# ivt33_kuznecov_list2_9var.net
KiCad netlist of a schematic drawn in Altium Designer
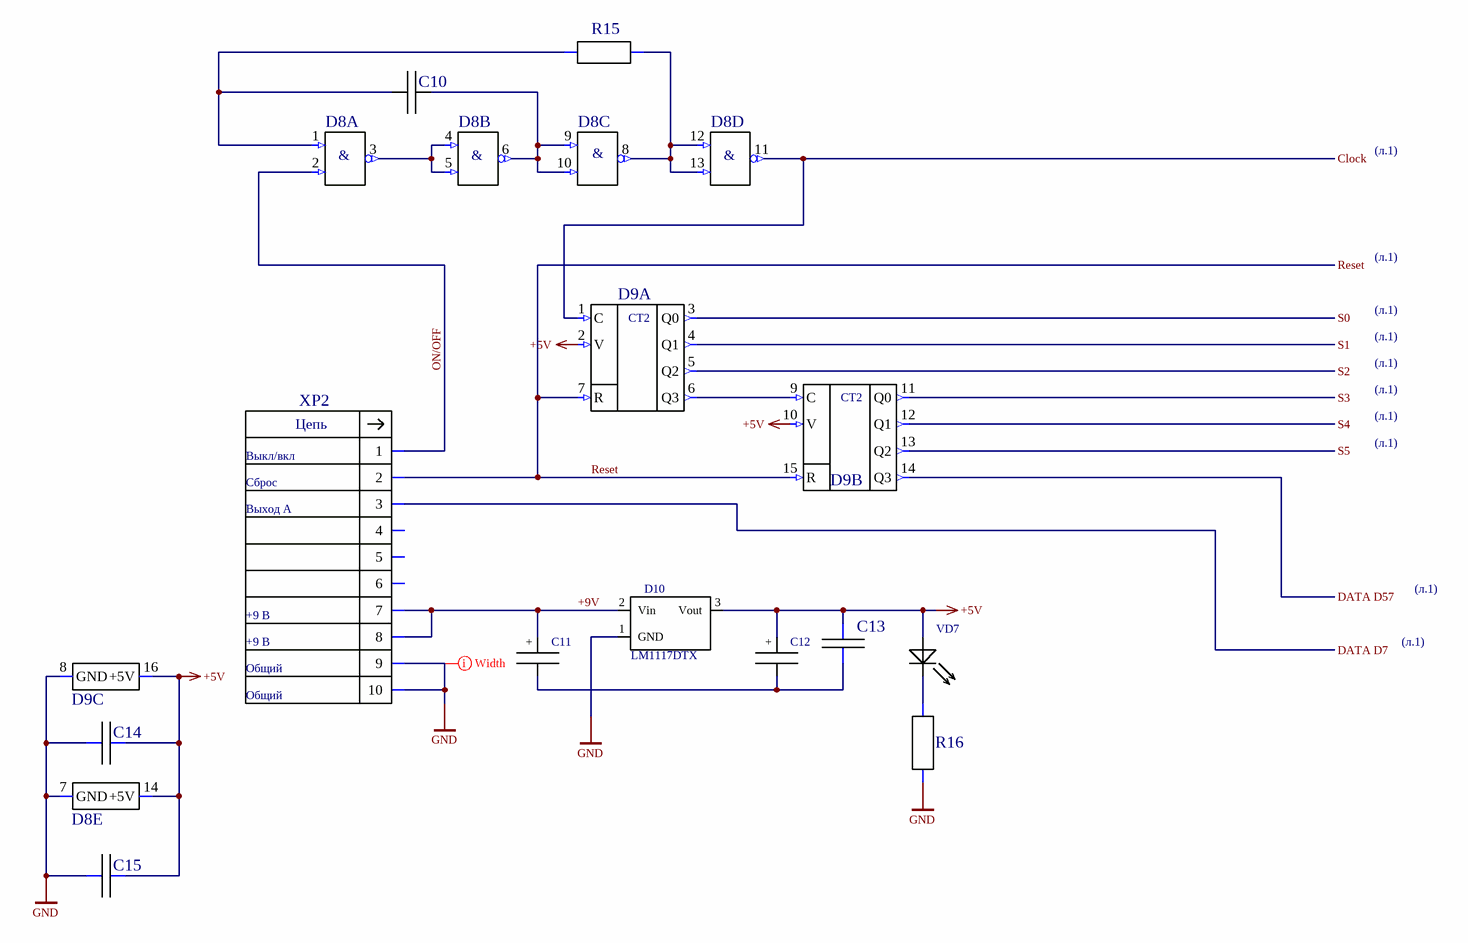
[diagram p0: ivt33_kuznecov_list2_9var.SchDoc]

(export (version "E")
  (design (tool "Eeschema 10.0.6"))
  (components
    (comp (ref "C10")
      (value "1210")
      (footprint "K10-79_3.2_2.5(1210)")
      (description "Чип конденсатор 1210 Н30 ряд Е6")
      (fields (field (name "MANUFACTURER") "ООО \"Кулон\"") (field (name "TOLERANCE") "±20%"))
      (libsource (lib "Int_Library_for_Lessons_3") (part "К10-79_1210_Н30"))
    )
    (comp (ref "C11")
      (value "*")
      (footprint "CA010M0010REB-0405")
      (description "Электролитический SND")
      (libsource (lib "*") (part "CA010M0010REB-0405"))
    )
    (comp (ref "C12")
      (value "*")
      (footprint "CA010M0010REB-0405")
      (description "Электролитический SND")
      (libsource (lib "*") (part "CA010M0010REB-0405"))
    )
    (comp (ref "C13")
      (value "~")
      (footprint "0805_N")
      (description "Чип конденсатор 0805 Н90 ряд Е6")
      (fields
        (field (name "MANUFACTURER") "ООО \"Кулон\"")
        (field (name "TOLERANCE") "+80%-20%")
        (field (name "CREATED_BY") "Желобаев")
      )
      (libsource (lib "Int_Library_for_Lessons_3") (part "К10-79_0805_Н90"))
    )
    (comp (ref "C14")
      (value "~")
      (footprint "0805_N")
      (description "Чип конденсатор 0805 Н90 ряд Е6")
      (fields
        (field (name "MANUFACTURER") "ООО \"Кулон\"")
        (field (name "TOLERANCE") "+80%-20%")
        (field (name "CREATED_BY") "Желобаев")
      )
      (libsource (lib "Int_Library_for_Lessons_3") (part "К10-79_0805_Н90"))
    )
    (comp (ref "C15")
      (value "~")
      (footprint "0805_N")
      (description "Чип конденсатор 0805 Н90 ряд Е6")
      (fields
        (field (name "MANUFACTURER") "ООО \"Кулон\"")
        (field (name "TOLERANCE") "+80%-20%")
        (field (name "CREATED_BY") "Желобаев")
      )
      (libsource (lib "Int_Library_for_Lessons_3") (part "К10-79_0805_Н90"))
    )
    (comp (ref "D8")
      (value "74AC00SC")
      (footprint "SO14-N")
      (description "4 элемента 2И-НЕ TTL SOIC-14")
      (fields (field (name "MANUFACTURER") "ON Semiconductor") (field (name "CREATED_BY") "Желобаев"))
      (libsource (lib "Int_Library_for_Lessons_3") (part "74AC00SC"))
    )
    (comp (ref "D9")
      (value "~")
      (footprint "SOIC-16W-N")
      (description "Два двоичных счетчика")
      (fields (field (name "MANUFACTURER") "Motorola") (field (name "CREATED_BY") "Желобаев"))
      (libsource (lib "Int_Library_for_Lessons_3") (part "MC14520BDWG"))
    )
    (comp (ref "D10")
      (value "LM1117DTX")
      (footprint "LM1117DTX-5.0/NOPB")
      (libsource (lib "*") (part "LT1117"))
    )
    (comp (ref "R15")
      (value "0805")
      (footprint "RES_0805_2012_N")
      (description "Резистор от 0,75 Ом до 2 МОм")
      (fields
        (field (name "MANUFACTURER") "ОАО \"НПО \"Эркон\"")
        (field (name "TOLERANCE") "5%")
        (field (name "CREATED_BY") "Желобаев")
      )
      (libsource (lib "Int_Library_for_Lessons_3") (part "Р1-12-0,125-5%"))
    )
    (comp (ref "R16")
      (value "~")
      (footprint "RES_0603_1608_N")
      (description "Резистор от 0,75 Ом до 10 МОм")
      (fields
        (field (name "MANUFACTURER") "ОАО \"НПО \"Эркон\"")
        (field (name "TOLERANCE") "5%")
        (field (name "CREATED_BY") "Желобаев")
      )
      (libsource (lib "Int_Library_for_Lessons_3") (part "Р1-12-0,1-5%"))
    )
    (comp (ref "VD7")
      (value "*")
      (footprint "LED_5mm")
      (description "Светодиод,5мм,жёлтый")
      (libsource (lib "*") (part "521-9466"))
    )
    (comp (ref "XP2")
      (value "TE_1-1634689-0")
      (footprint "BH-10R")
      (description "Вилка типа BH-10R угловая правая двухрядная 2х5х2.54")
      (fields (field (name "MANUFACTURER") "TE Connectivity") (field (name "CREATED_BY") "Желобаев"))
      (libsource (lib "Int_Library_for_Lessons_3") (part "TE_1-1634689-0"))
    )
  )
  (nets
    (net (code "1") (name "+5V") (class "Default")
      (node (ref "C12") (pin "+") (pinfunction "+_+") (pintype "passive"))
      (node (ref "C13") (pin "2") (pinfunction "2_2") (pintype "passive"))
      (node (ref "C14") (pin "2") (pinfunction "2_2") (pintype "passive"))
      (node (ref "C15") (pin "2") (pinfunction "2_2") (pintype "passive"))
      (node (ref "D10") (pin "3") (pinfunction "Vout_3") (pintype "power_in"))
      (node (ref "D8") (pin "14") (pinfunction "+5V_14") (pintype "power_in"))
      (node (ref "D9") (pin "10") (pinfunction "V_10") (pintype "input"))
      (node (ref "D9") (pin "16") (pinfunction "+5V_16") (pintype "power_in"))
      (node (ref "D9") (pin "2") (pinfunction "V_2") (pintype "input"))
      (node (ref "VD7") (pin "A") (pinfunction "A_A") (pintype "passive"))
    )
    (net (code "2") (name "/+9V") (class "Default")
      (node (ref "C11") (pin "+") (pinfunction "+_+") (pintype "passive"))
      (node (ref "D10") (pin "2") (pinfunction "Vin_2") (pintype "power_in"))
      (node (ref "XP2") (pin "7") (pinfunction "7_7") (pintype "passive"))
      (node (ref "XP2") (pin "8") (pinfunction "8_8") (pintype "passive"))
    )
    (net (code "3") (name "/Clock") (class "Default")
      (node (ref "D8") (pin "11") (pinfunction "Out_11") (pintype "output"))
      (node (ref "D9") (pin "1") (pinfunction "C_1") (pintype "input"))
    )
    (net (code "4") (name "/DATA D7") (class "Default")
      (node (ref "XP2") (pin "3") (pinfunction "3_3") (pintype "passive"))
    )
    (net (code "5") (name "/DATA D57") (class "Default")
      (node (ref "D9") (pin "14") (pinfunction "Q3_14") (pintype "output"))
    )
    (net (code "6") (name "/ON{slash}OFF") (class "Default")
      (node (ref "D8") (pin "2") (pinfunction "In2_2") (pintype "input"))
      (node (ref "XP2") (pin "1") (pinfunction "1_1") (pintype "passive"))
    )
    (net (code "7") (name "/Reset") (class "Default")
      (node (ref "D9") (pin "15") (pinfunction "R_15") (pintype "input"))
      (node (ref "D9") (pin "7") (pinfunction "R_7") (pintype "input"))
      (node (ref "XP2") (pin "2") (pinfunction "2_2") (pintype "passive"))
    )
    (net (code "8") (name "/S0") (class "Default")
      (node (ref "D9") (pin "3") (pinfunction "Q0_3") (pintype "output"))
    )
    (net (code "9") (name "/S1") (class "Default")
      (node (ref "D9") (pin "4") (pinfunction "Q1_4") (pintype "output"))
    )
    (net (code "10") (name "/S2") (class "Default")
      (node (ref "D9") (pin "5") (pinfunction "Q2_5") (pintype "output"))
    )
    (net (code "11") (name "/S3") (class "Default")
      (node (ref "D9") (pin "11") (pinfunction "Q0_11") (pintype "output"))
    )
    (net (code "12") (name "/S4") (class "Default")
      (node (ref "D9") (pin "12") (pinfunction "Q1_12") (pintype "output"))
    )
    (net (code "13") (name "/S5") (class "Default")
      (node (ref "D9") (pin "13") (pinfunction "Q2_13") (pintype "output"))
    )
    (net (code "14") (name "GND") (class "Default")
      (node (ref "C14") (pin "1") (pinfunction "1_1") (pintype "passive"))
      (node (ref "C15") (pin "1") (pinfunction "1_1") (pintype "passive"))
      (node (ref "D10") (pin "1") (pinfunction "GND_1") (pintype "power_in"))
      (node (ref "D8") (pin "7") (pinfunction "GND_7") (pintype "power_in"))
      (node (ref "D9") (pin "8") (pinfunction "GND_8") (pintype "power_in"))
      (node (ref "R16") (pin "1") (pinfunction "1_1") (pintype "passive"))
      (node (ref "XP2") (pin "10") (pinfunction "10_10") (pintype "passive"))
      (node (ref "XP2") (pin "9") (pinfunction "9_9") (pintype "passive"))
    )
    (net (code "15") (name "Net-(C11-Pad-)") (class "Default")
      (node (ref "C11") (pin "-") (pinfunction "-_-") (pintype "passive"))
      (node (ref "C12") (pin "-") (pinfunction "-_-") (pintype "passive"))
      (node (ref "C13") (pin "1") (pinfunction "1_1") (pintype "passive"))
    )
    (net (code "16") (name "Net-(D8A-In1)") (class "Default")
      (node (ref "C10") (pin "1") (pinfunction "1_1") (pintype "passive"))
      (node (ref "D8") (pin "1") (pinfunction "In1_1") (pintype "input"))
      (node (ref "R15") (pin "1") (pinfunction "1_1") (pintype "passive"))
    )
    (net (code "17") (name "Net-(D8A-Out)") (class "Default")
      (node (ref "D8") (pin "3") (pinfunction "Out_3") (pintype "output"))
      (node (ref "D8") (pin "4") (pinfunction "In1_4") (pintype "input"))
      (node (ref "D8") (pin "5") (pinfunction "In2_5") (pintype "input"))
    )
    (net (code "18") (name "Net-(D8B-Out)") (class "Default")
      (node (ref "C10") (pin "2") (pinfunction "2_2") (pintype "passive"))
      (node (ref "D8") (pin "10") (pinfunction "In2_10") (pintype "input"))
      (node (ref "D8") (pin "6") (pinfunction "Out_6") (pintype "output"))
      (node (ref "D8") (pin "9") (pinfunction "In1_9") (pintype "input"))
    )
    (net (code "19") (name "Net-(D8C-Out)") (class "Default")
      (node (ref "D8") (pin "12") (pinfunction "In1_12") (pintype "input"))
      (node (ref "D8") (pin "13") (pinfunction "In2_13") (pintype "input"))
      (node (ref "D8") (pin "8") (pinfunction "Out_8") (pintype "output"))
      (node (ref "R15") (pin "2") (pinfunction "2_2") (pintype "passive"))
    )
    (net (code "20") (name "Net-(D9A-Q3)") (class "Default")
      (node (ref "D9") (pin "6") (pinfunction "Q3_6") (pintype "output"))
      (node (ref "D9") (pin "9") (pinfunction "C_9") (pintype "input"))
    )
    (net (code "21") (name "Net-(R16-Pad2)") (class "Default")
      (node (ref "R16") (pin "2") (pinfunction "2_2") (pintype "passive"))
      (node (ref "VD7") (pin "C") (pinfunction "C_C") (pintype "passive"))
    )
    (net (code "22") (name "unconnected-(XP2-Pad4)") (class "Default")
      (node (ref "XP2") (pin "4") (pinfunction "4_4") (pintype "passive"))
    )
    (net (code "23") (name "unconnected-(XP2-Pad5)") (class "Default")
      (node (ref "XP2") (pin "5") (pinfunction "5_5") (pintype "passive"))
    )
    (net (code "24") (name "unconnected-(XP2-Pad6)") (class "Default")
      (node (ref "XP2") (pin "6") (pinfunction "6_6") (pintype "passive"))
    )
  )
)
